# 2.net
KiCad netlist of a schematic drawn in EAGLE
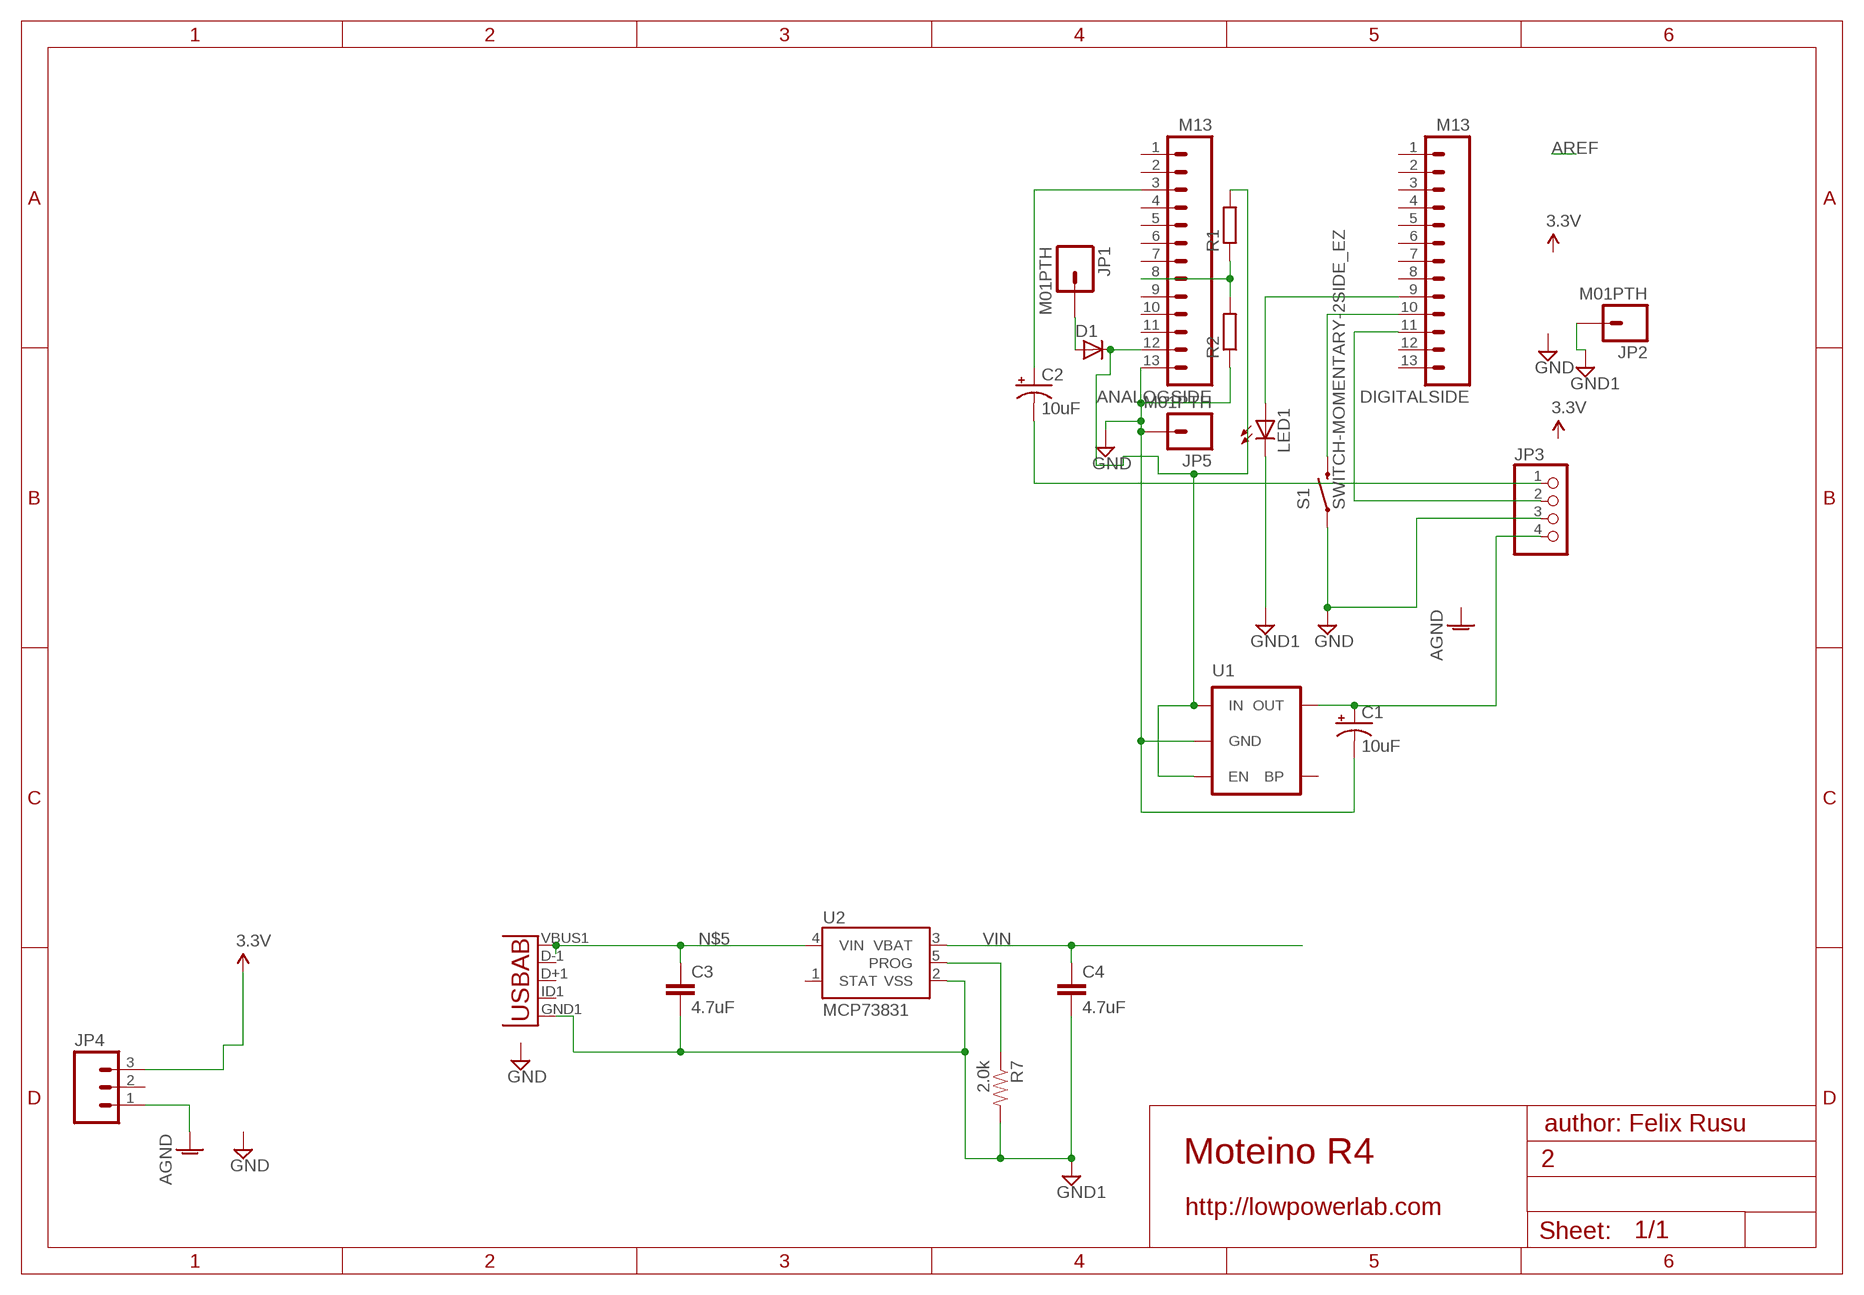
[diagram p0: schematic, sheet 1]

(export (version "E")
  (design (tool "Eeschema 10.0.6"))
  (components
    (comp (ref "ANALOGSIDE")
      (value "M13")
      (footprint "eagle-import:1X13")
      (libsource (lib "eagle-import") (part "M13"))
    )
    (comp (ref "C1")
      (value "10uF")
      (footprint "eagle-import:EIA3216")
      (libsource (lib "eagle-import") (part "10UF-16V-10%(TANT)"))
    )
    (comp (ref "C2")
      (value "10uF")
      (footprint "eagle-import:EIA3216")
      (libsource (lib "eagle-import") (part "10UF-16V-10%(TANT)"))
    )
    (comp (ref "C3")
      (value "4.7uF")
      (footprint "eagle-import:0603-CAP")
      (libsource (lib "eagle-import") (part "4.7UF-6.3V-10%(0603)0603"))
    )
    (comp (ref "C4")
      (value "4.7uF")
      (footprint "eagle-import:0603-CAP")
      (libsource (lib "eagle-import") (part "4.7UF-6.3V-10%(0603)0603"))
    )
    (comp (ref "D1")
      (value "D-MLL-34")
      (footprint "eagle-import:MELF-MLL34")
      (libsource (lib "eagle-import") (part "D-MLL-34"))
    )
    (comp (ref "DIGITALSIDE")
      (value "M13")
      (footprint "eagle-import:1X13")
      (libsource (lib "eagle-import") (part "M13"))
    )
    (comp (ref "JP1")
      (value "M01PTH")
      (footprint "eagle-import:1X01")
      (libsource (lib "eagle-import") (part "M01PTH"))
    )
    (comp (ref "JP2")
      (value "M01PTH")
      (footprint "eagle-import:1X01")
      (libsource (lib "eagle-import") (part "M01PTH"))
    )
    (comp (ref "JP3")
      (value "PINHD-1X4")
      (footprint "eagle-import:1X04")
      (libsource (lib "eagle-import") (part "PINHD-1X4"))
    )
    (comp (ref "JP4")
      (value "M03PTH")
      (footprint "eagle-import:1X03")
      (libsource (lib "eagle-import") (part "M03PTH"))
    )
    (comp (ref "JP5")
      (value "M01PTH")
      (footprint "eagle-import:1X01")
      (libsource (lib "eagle-import") (part "M01PTH"))
    )
    (comp (ref "JP9")
      (value "Micro USB")
      (footprint "eagle-import:USB-AB-MICRO-SMD_V03")
      (libsource (lib "eagle-import") (part "USB-ABCONN-11794"))
    )
    (comp (ref "LED1")
      (value "LED3MM")
      (footprint "eagle-import:LED3MM")
      (libsource (lib "eagle-import") (part "LED3MM"))
    )
    (comp (ref "R1")
      (value "R-EU_0204/7")
      (footprint "eagle-import:0204_7")
      (libsource (lib "eagle-import") (part "R-EU_0204/7"))
    )
    (comp (ref "R2")
      (value "R-EU_0204/7")
      (footprint "eagle-import:0204_7")
      (libsource (lib "eagle-import") (part "R-EU_0204/7"))
    )
    (comp (ref "R7")
      (value "2.0k")
      (footprint "eagle-import:0603-RES")
      (libsource (lib "eagle-import") (part "2.0KOHM1/10W5%(0603)"))
    )
    (comp (ref "S1")
      (value "SWITCH-MOMENTARY-2SIDE_EZ")
      (footprint "eagle-import:TACTILE-PTH-SIDEEZ")
      (libsource (lib "eagle-import") (part "SWITCH-MOMENTARY-2SIDE_EZ"))
    )
    (comp (ref "U1")
      (value "MIC52055V")
      (footprint "eagle-import:SOT23-5@1")
      (libsource (lib "eagle-import") (part "MIC52055V"))
    )
    (comp (ref "U2")
      (value "MCP73831")
      (footprint "eagle-import:SOT23-5")
      (libsource (lib "eagle-import") (part "MCP73831"))
    )
  )
  (nets
    (net (code "2") (name "/N$5") (class "Default")
      (node (ref "ANALOGSIDE") (pin "12") (pinfunction "12_12") (pintype "passive"))
      (node (ref "C3") (pin "1") (pinfunction "1_1") (pintype "passive"))
      (node (ref "D1") (pin "1") (pinfunction "C_1") (pintype "passive"))
      (node (ref "JP9") (pin "VBUS1") (pinfunction "VBUS_VBUS1") (pintype "bidirectional"))
      (node (ref "R1") (pin "2") (pinfunction "2_2") (pintype "passive"))
      (node (ref "U1") (pin "1") (pinfunction "IN_1") (pintype "input"))
      (node (ref "U1") (pin "3") (pinfunction "EN_3") (pintype "input"))
      (node (ref "U2") (pin "4") (pinfunction "VIN_4") (pintype "power_in"))
    )
    (net (code "3") (name "/VIN") (class "Default")
      (node (ref "C4") (pin "1") (pinfunction "1_1") (pintype "passive"))
      (node (ref "U2") (pin "3") (pinfunction "VBAT_3") (pintype "power_in"))
    )
    (net (code "4") (name "3.3V") (class "Default")
      (node (ref "JP4") (pin "3") (pinfunction "3_3") (pintype "passive"))
    )
    (net (code "5") (name "AGND") (class "Default")
      (node (ref "JP4") (pin "1") (pinfunction "1_1") (pintype "passive"))
    )
    (net (code "6") (name "GND") (class "Default")
      (node (ref "ANALOGSIDE") (pin "13") (pinfunction "13_13") (pintype "passive"))
      (node (ref "C1") (pin "C") (pinfunction "-_C") (pintype "passive"))
      (node (ref "JP3") (pin "3") (pinfunction "3_3") (pintype "passive"))
      (node (ref "JP5") (pin "1") (pinfunction "1_1") (pintype "passive"))
      (node (ref "R2") (pin "1") (pinfunction "1_1") (pintype "passive"))
      (node (ref "S1") (pin "1") (pinfunction "1_1") (pintype "passive"))
      (node (ref "U1") (pin "2") (pinfunction "GND_2") (pintype "input"))
    )
    (net (code "7") (name "GND1") (class "Default")
      (node (ref "C3") (pin "2") (pinfunction "2_2") (pintype "passive"))
      (node (ref "C4") (pin "2") (pinfunction "2_2") (pintype "passive"))
      (node (ref "JP2") (pin "1") (pinfunction "1_1") (pintype "passive"))
      (node (ref "JP9") (pin "GND1") (pinfunction "GND_GND1") (pintype "bidirectional"))
      (node (ref "LED1") (pin "K") (pinfunction "C_K") (pintype "passive"))
      (node (ref "R7") (pin "2") (pinfunction "2_2") (pintype "passive"))
      (node (ref "U2") (pin "2") (pinfunction "VSS_2") (pintype "power_in"))
    )
    (net (code "8") (name "Net-(ANALOGSIDE-Pad8)") (class "Default")
      (node (ref "ANALOGSIDE") (pin "8") (pinfunction "8_8") (pintype "passive"))
      (node (ref "R1") (pin "1") (pinfunction "1_1") (pintype "passive"))
      (node (ref "R2") (pin "2") (pinfunction "2_2") (pintype "passive"))
    )
    (net (code "9") (name "Net-(C1-+)") (class "Default")
      (node (ref "C1") (pin "A") (pinfunction "+_A") (pintype "passive"))
      (node (ref "JP3") (pin "4") (pinfunction "4_4") (pintype "passive"))
      (node (ref "U1") (pin "5") (pinfunction "OUT_5") (pintype "passive"))
    )
    (net (code "10") (name "Net-(C2-+)") (class "Default")
      (node (ref "ANALOGSIDE") (pin "3") (pinfunction "3_3") (pintype "passive"))
      (node (ref "C2") (pin "A") (pinfunction "+_A") (pintype "passive"))
    )
    (net (code "11") (name "Net-(C2--)") (class "Default")
      (node (ref "C2") (pin "C") (pinfunction "-_C") (pintype "passive"))
      (node (ref "JP3") (pin "1") (pinfunction "1_1") (pintype "passive"))
    )
    (net (code "12") (name "Net-(D1-A)") (class "Default")
      (node (ref "D1") (pin "2") (pinfunction "A_2") (pintype "passive"))
      (node (ref "JP1") (pin "1") (pinfunction "1_1") (pintype "passive"))
    )
    (net (code "13") (name "Net-(DIGITALSIDE-Pad9)") (class "Default")
      (node (ref "DIGITALSIDE") (pin "9") (pinfunction "9_9") (pintype "passive"))
      (node (ref "LED1") (pin "A") (pinfunction "A_A") (pintype "passive"))
    )
    (net (code "14") (name "Net-(DIGITALSIDE-Pad10)") (class "Default")
      (node (ref "DIGITALSIDE") (pin "10") (pinfunction "10_10") (pintype "passive"))
      (node (ref "S1") (pin "2") (pinfunction "2_2") (pintype "passive"))
    )
    (net (code "15") (name "Net-(DIGITALSIDE-Pad11)") (class "Default")
      (node (ref "DIGITALSIDE") (pin "11") (pinfunction "11_11") (pintype "passive"))
      (node (ref "JP3") (pin "2") (pinfunction "2_2") (pintype "passive"))
    )
    (net (code "16") (name "Net-(U2-PROG)") (class "Default")
      (node (ref "R7") (pin "1") (pinfunction "1_1") (pintype "passive"))
      (node (ref "U2") (pin "5") (pinfunction "PROG_5") (pintype "input"))
    )
    (net (code "17") (name "unconnected-(ANALOGSIDE-Pad1)") (class "Default")
      (node (ref "ANALOGSIDE") (pin "1") (pinfunction "1_1") (pintype "passive"))
    )
    (net (code "18") (name "unconnected-(ANALOGSIDE-Pad2)") (class "Default")
      (node (ref "ANALOGSIDE") (pin "2") (pinfunction "2_2") (pintype "passive"))
    )
    (net (code "19") (name "unconnected-(ANALOGSIDE-Pad4)") (class "Default")
      (node (ref "ANALOGSIDE") (pin "4") (pinfunction "4_4") (pintype "passive"))
    )
    (net (code "20") (name "unconnected-(ANALOGSIDE-Pad5)") (class "Default")
      (node (ref "ANALOGSIDE") (pin "5") (pinfunction "5_5") (pintype "passive"))
    )
    (net (code "21") (name "unconnected-(ANALOGSIDE-Pad6)") (class "Default")
      (node (ref "ANALOGSIDE") (pin "6") (pinfunction "6_6") (pintype "passive"))
    )
    (net (code "22") (name "unconnected-(ANALOGSIDE-Pad7)") (class "Default")
      (node (ref "ANALOGSIDE") (pin "7") (pinfunction "7_7") (pintype "passive"))
    )
    (net (code "23") (name "unconnected-(ANALOGSIDE-Pad9)") (class "Default")
      (node (ref "ANALOGSIDE") (pin "9") (pinfunction "9_9") (pintype "passive"))
    )
    (net (code "24") (name "unconnected-(ANALOGSIDE-Pad10)") (class "Default")
      (node (ref "ANALOGSIDE") (pin "10") (pinfunction "10_10") (pintype "passive"))
    )
    (net (code "25") (name "unconnected-(ANALOGSIDE-Pad11)") (class "Default")
      (node (ref "ANALOGSIDE") (pin "11") (pinfunction "11_11") (pintype "passive"))
    )
    (net (code "26") (name "unconnected-(DIGITALSIDE-Pad1)") (class "Default")
      (node (ref "DIGITALSIDE") (pin "1") (pinfunction "1_1") (pintype "passive"))
    )
    (net (code "27") (name "unconnected-(DIGITALSIDE-Pad2)") (class "Default")
      (node (ref "DIGITALSIDE") (pin "2") (pinfunction "2_2") (pintype "passive"))
    )
    (net (code "28") (name "unconnected-(DIGITALSIDE-Pad3)") (class "Default")
      (node (ref "DIGITALSIDE") (pin "3") (pinfunction "3_3") (pintype "passive"))
    )
    (net (code "29") (name "unconnected-(DIGITALSIDE-Pad4)") (class "Default")
      (node (ref "DIGITALSIDE") (pin "4") (pinfunction "4_4") (pintype "passive"))
    )
    (net (code "30") (name "unconnected-(DIGITALSIDE-Pad5)") (class "Default")
      (node (ref "DIGITALSIDE") (pin "5") (pinfunction "5_5") (pintype "passive"))
    )
    (net (code "31") (name "unconnected-(DIGITALSIDE-Pad6)") (class "Default")
      (node (ref "DIGITALSIDE") (pin "6") (pinfunction "6_6") (pintype "passive"))
    )
    (net (code "32") (name "unconnected-(DIGITALSIDE-Pad7)") (class "Default")
      (node (ref "DIGITALSIDE") (pin "7") (pinfunction "7_7") (pintype "passive"))
    )
    (net (code "33") (name "unconnected-(DIGITALSIDE-Pad8)") (class "Default")
      (node (ref "DIGITALSIDE") (pin "8") (pinfunction "8_8") (pintype "passive"))
    )
    (net (code "34") (name "unconnected-(DIGITALSIDE-Pad12)") (class "Default")
      (node (ref "DIGITALSIDE") (pin "12") (pinfunction "12_12") (pintype "passive"))
    )
    (net (code "35") (name "unconnected-(DIGITALSIDE-Pad13)") (class "Default")
      (node (ref "DIGITALSIDE") (pin "13") (pinfunction "13_13") (pintype "passive"))
    )
    (net (code "36") (name "unconnected-(JP4-Pad2)") (class "Default")
      (node (ref "JP4") (pin "2") (pinfunction "2_2") (pintype "passive"))
    )
    (net (code "37") (name "unconnected-(JP9-D+-PadD+1)") (class "Default")
      (node (ref "JP9") (pin "D+1") (pinfunction "D+_D+1") (pintype "bidirectional"))
    )
    (net (code "38") (name "unconnected-(JP9-D--PadD-1)") (class "Default")
      (node (ref "JP9") (pin "D-1") (pinfunction "D-_D-1") (pintype "bidirectional"))
    )
    (net (code "39") (name "unconnected-(JP9-USBID-PadID1)") (class "Default")
      (node (ref "JP9") (pin "ID1") (pinfunction "USBID_ID1") (pintype "bidirectional"))
    )
    (net (code "40") (name "unconnected-(U1-BP-Pad4)") (class "Default")
      (node (ref "U1") (pin "4") (pinfunction "BP_4") (pintype "input"))
    )
    (net (code "41") (name "unconnected-(U2-STAT-Pad1)") (class "Default")
      (node (ref "U2") (pin "1") (pinfunction "STAT_1") (pintype "output"))
    )
  )
)
